# DCDC_stepup.net
KiCad netlist of a schematic drawn in Altium Designer
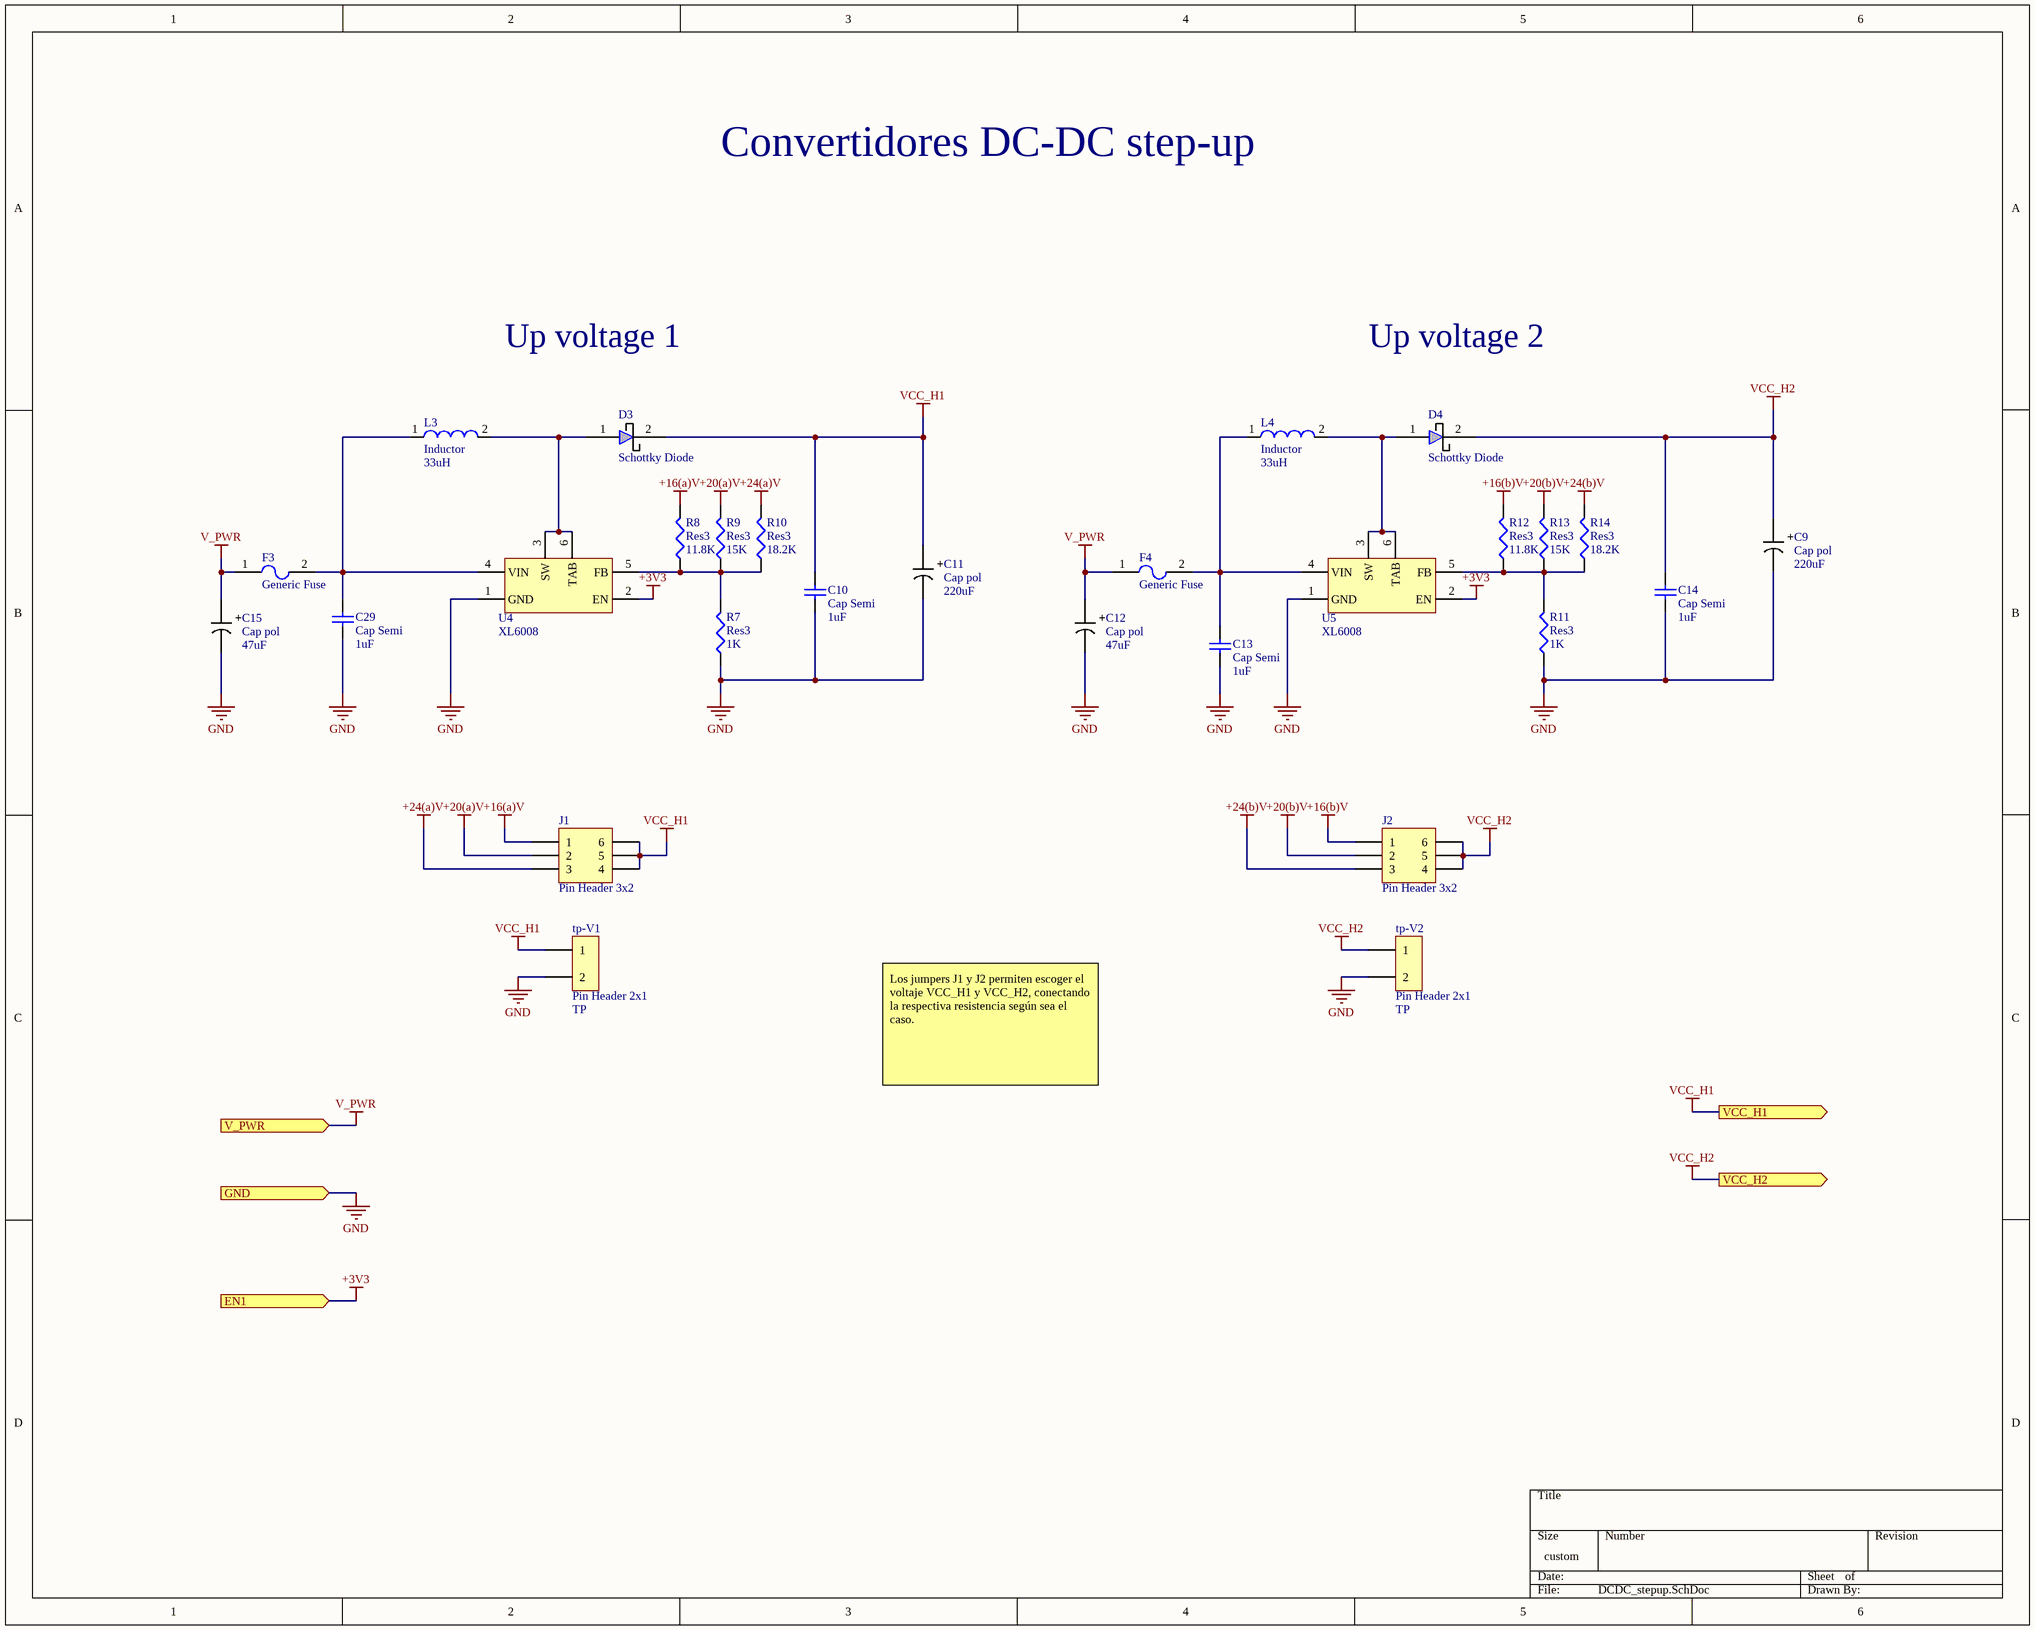
[diagram p0: DCDC_stepup.SchDoc]

(export (version "E")
  (design (tool "Eeschema 10.0.6"))
  (components
    (comp (ref "C9")
      (value "Cap pol")
      (footprint "CAP_SMD_Electrolytic_10x10")
      (description "Electrolytic Aluminium Capacitor")
      (fields
        (field (name "MANUFACTURER") "Lelon")
        (field (name "MANUFACTURER PART NUMBER") "VE-221M1HTR-1010")
        (field (name "ALTIUM_VALUE") "220uF")
      )
      (libsource (lib "IoWLabs") (part "Cap pol"))
    )
    (comp (ref "C10")
      (value "Cap Semi")
      (footprint "1608[0603]")
      (description "Capacitor (Semiconductor SIM Model)")
      (fields
        (field (name "ALTIUM_VALUE") "1uF")
        (field (name "MANUFACTURER") "Samsung Electro-Mechanics")
        (field (name "MANUFACTURER PART NUMBER") "CL10A105KB8NNNC")
        (field (name "PUBLISHER") "Altium Limited")
      )
      (libsource (lib "Miscellaneous Devices") (part "Cap Semi"))
    )
    (comp (ref "C11")
      (value "Cap pol")
      (footprint "CAP_SMD_Electrolytic_10x10")
      (description "Electrolytic Aluminium Capacitor")
      (fields
        (field (name "MANUFACTURER") "Lelon")
        (field (name "MANUFACTURER PART NUMBER") "VE-221M1HTR-1010")
        (field (name "ALTIUM_VALUE") "220uF")
      )
      (libsource (lib "IoWLabs") (part "Cap pol"))
    )
    (comp (ref "C12")
      (value "Cap pol")
      (footprint "CAP_SMD_Electrolytic_10x10")
      (description "Electrolytic Aluminium Capacitor")
      (fields
        (field (name "MANUFACTURER") "Lelon")
        (field (name "MANUFACTURER PART NUMBER") "VEJ470M1HTR-1010")
        (field (name "ALTIUM_VALUE") "47uF")
      )
      (libsource (lib "IoWLabs") (part "Cap pol"))
    )
    (comp (ref "C13")
      (value "Cap Semi")
      (footprint "1608[0603]")
      (description "Capacitor (Semiconductor SIM Model)")
      (fields
        (field (name "ALTIUM_VALUE") "1uF")
        (field (name "MANUFACTURER") "Samsung Electro-Mechanics")
        (field (name "MANUFACTURER PART NUMBER") "CL10A105KB8NNNC")
        (field (name "PUBLISHER") "Altium Limited")
      )
      (libsource (lib "Miscellaneous Devices") (part "Cap Semi"))
    )
    (comp (ref "C14")
      (value "Cap Semi")
      (footprint "1608[0603]")
      (description "Capacitor (Semiconductor SIM Model)")
      (fields
        (field (name "ALTIUM_VALUE") "1uF")
        (field (name "MANUFACTURER") "Samsung Electro-Mechanics")
        (field (name "MANUFACTURER PART NUMBER") "CL10A105KB8NNNC")
        (field (name "PUBLISHER") "Altium Limited")
      )
      (libsource (lib "Miscellaneous Devices") (part "Cap Semi"))
    )
    (comp (ref "C15")
      (value "Cap pol")
      (footprint "CAP_SMD_Electrolytic_10x10")
      (description "Electrolytic Aluminium Capacitor")
      (fields
        (field (name "MANUFACTURER") "Lelon")
        (field (name "MANUFACTURER PART NUMBER") "VEJ470M1HTR-1010")
        (field (name "ALTIUM_VALUE") "47uF")
      )
      (libsource (lib "IoWLabs") (part "Cap pol"))
    )
    (comp (ref "C29")
      (value "Cap Semi")
      (footprint "1608[0603]")
      (description "Capacitor (Semiconductor SIM Model)")
      (fields
        (field (name "ALTIUM_VALUE") "1uF")
        (field (name "MANUFACTURER") "Samsung Electro-Mechanics")
        (field (name "MANUFACTURER PART NUMBER") "CL10A105KB8NNNC")
        (field (name "PUBLISHER") "Altium Limited")
      )
      (libsource (lib "Miscellaneous Devices") (part "Cap Semi"))
    )
    (comp (ref "D3")
      (value "Schottky Diode")
      (footprint "SMB_L4.6-W3.6-LS5.3-RD")
      (description "Schottky Diodes")
      (fields
        (field (name "MANUFACTURER") "MCC(Micro Commercial Components)")
        (field (name "MANUFACTURER PART NUMBER") "SK32B-LTP")
      )
      (libsource (lib "IoWLabs") (part "Schottky Diode"))
    )
    (comp (ref "D4")
      (value "Schottky Diode")
      (footprint "SMB_L4.6-W3.6-LS5.3-RD")
      (description "Schottky Diodes")
      (fields
        (field (name "MANUFACTURER") "MCC(Micro Commercial Components)")
        (field (name "MANUFACTURER PART NUMBER") "SK32B-LTP")
      )
      (libsource (lib "IoWLabs") (part "Schottky Diode"))
    )
    (comp (ref "F3")
      (value "Generic Fuse")
      (footprint "F1206")
      (description "SMD Fuse")
      (fields (field (name "MANUFACTURER") "AEM") (field (name "MANUFACTURER PART NUMBER") "F1206VH4500TM"))
      (libsource (lib "IoWLabs") (part "FUSE"))
    )
    (comp (ref "F4")
      (value "Generic Fuse")
      (footprint "F1206")
      (description "SMD Fuse")
      (fields (field (name "MANUFACTURER") "AEM") (field (name "MANUFACTURER PART NUMBER") "F1206VH4500TM"))
      (libsource (lib "IoWLabs") (part "FUSE"))
    )
    (comp (ref "J1")
      (value "Pin Header 3x2")
      (footprint "HDR-TH_6P-P2.54-V-R2-C3-S2.54_A2541WV-2X3P")
      (description "Pin Header 6pos, 2 row, 2.54 pitch")
      (fields
        (field (name "MANUFACTURER") "CJT(Changjiang Connectors)")
        (field (name "MANUFACTURER PART NUMBER") "A2541WV-2x3P")
      )
      (libsource (lib "IoWLabsConnectors") (part "Header - 3x2c"))
    )
    (comp (ref "J2")
      (value "Pin Header 3x2")
      (footprint "HDR-TH_6P-P2.54-V-R2-C3-S2.54_A2541WV-2X3P")
      (description "Pin Header 6pos, 2 row, 2.54 pitch")
      (fields
        (field (name "MANUFACTURER") "CJT(Changjiang Connectors)")
        (field (name "MANUFACTURER PART NUMBER") "A2541WV-2x3P")
      )
      (libsource (lib "IoWLabsConnectors") (part "Header - 3x2c"))
    )
    (comp (ref "L3")
      (value "Inductor")
      (footprint "IND-SMD_L12.3-W12.3")
      (description "Inductor SMD")
      (fields
        (field (name "MANUFACTURER") "SXN(Shun Xiang Nuo Elec)")
        (field (name "MANUFACTURER PART NUMBER") "SMDRI127-330MT")
        (field (name "ALTIUM_VALUE") "33uH")
      )
      (libsource (lib "IoWLabs") (part "Inductor"))
    )
    (comp (ref "L4")
      (value "Inductor")
      (footprint "IND-SMD_L12.3-W12.3")
      (description "Inductor SMD")
      (fields
        (field (name "MANUFACTURER") "SXN(Shun Xiang Nuo Elec)")
        (field (name "MANUFACTURER PART NUMBER") "SMDRI127-330MT")
        (field (name "ALTIUM_VALUE") "33uH")
      )
      (libsource (lib "IoWLabs") (part "Inductor"))
    )
    (comp (ref "R7")
      (value "Res3")
      (footprint "J1-0603")
      (description "Resistor")
      (fields
        (field (name "ALTIUM_VALUE") "1K")
        (field (name "MANUFACTURER") "KAMAYA")
        (field (name "MANUFACTURER PART NUMBER") "RMC16K102FTP")
        (field (name "PUBLISHER") "Altium Limited")
      )
      (libsource (lib "Miscellaneous Devices") (part "Res3"))
    )
    (comp (ref "R8")
      (value "Res3")
      (footprint "J1-0603")
      (description "Resistor")
      (fields
        (field (name "ALTIUM_VALUE") "11.8K")
        (field (name "MANUFACTURER PART NUMBER") "AC0603FR-0711K8L")
        (field (name "MANUFACTURER") "YAGEO")
        (field (name "PUBLISHER") "Altium Limited")
      )
      (libsource (lib "Miscellaneous Devices") (part "Res3"))
    )
    (comp (ref "R9")
      (value "Res3")
      (footprint "J1-0603")
      (description "Resistor")
      (fields
        (field (name "ALTIUM_VALUE") "15K")
        (field (name "MANUFACTURER") "YAGEO")
        (field (name "MANUFACTURER PART NUMBER") "RC0603FR-0715KL")
        (field (name "PUBLISHER") "Altium Limited")
      )
      (libsource (lib "Miscellaneous Devices") (part "Res3"))
    )
    (comp (ref "R10")
      (value "Res3")
      (footprint "J1-0603")
      (description "Resistor")
      (fields
        (field (name "ALTIUM_VALUE") "18.2K")
        (field (name "MANUFACTURER") "RALEC")
        (field (name "MANUFACTURER PART NUMBER") "RTT031822FTP")
        (field (name "PUBLISHER") "Altium Limited")
      )
      (libsource (lib "Miscellaneous Devices") (part "Res3"))
    )
    (comp (ref "R11")
      (value "Res3")
      (footprint "J1-0603")
      (description "Resistor")
      (fields
        (field (name "ALTIUM_VALUE") "1K")
        (field (name "MANUFACTURER") "KAMAYA")
        (field (name "MANUFACTURER PART NUMBER") "RMC16K102FTP")
        (field (name "PUBLISHER") "Altium Limited")
      )
      (libsource (lib "Miscellaneous Devices") (part "Res3"))
    )
    (comp (ref "R12")
      (value "Res3")
      (footprint "J1-0603")
      (description "Resistor")
      (fields
        (field (name "ALTIUM_VALUE") "11.8K")
        (field (name "MANUFACTURER PART NUMBER") "AC0603FR-0711K8L")
        (field (name "MANUFACTURER") "YAGEO")
        (field (name "PUBLISHER") "Altium Limited")
      )
      (libsource (lib "Miscellaneous Devices") (part "Res3"))
    )
    (comp (ref "R13")
      (value "Res3")
      (footprint "J1-0603")
      (description "Resistor")
      (fields
        (field (name "ALTIUM_VALUE") "15K")
        (field (name "MANUFACTURER") "YAGEO")
        (field (name "MANUFACTURER PART NUMBER") "RC0603FR-0715KL")
        (field (name "PUBLISHER") "Altium Limited")
      )
      (libsource (lib "Miscellaneous Devices") (part "Res3"))
    )
    (comp (ref "R14")
      (value "Res3")
      (footprint "J1-0603")
      (description "Resistor")
      (fields
        (field (name "ALTIUM_VALUE") "18.2K")
        (field (name "MANUFACTURER") "RALEC")
        (field (name "MANUFACTURER PART NUMBER") "RTT031822FTP")
        (field (name "PUBLISHER") "Altium Limited")
      )
      (libsource (lib "Miscellaneous Devices") (part "Res3"))
    )
    (comp (ref "tp-V1")
      (value "Pin Header 2x1")
      (footprint "HDR-TH_P2.54-H-M_A2541WV-2P")
      (description "Pin Header 2pos, 1 row, 2.54 pitch")
      (fields
        (field (name "MANUFACTURER") "CJT(Changjiang Connectors)")
        (field (name "MANUFACTURER PART NUMBER") "A2541WV-2P")
      )
      (libsource (lib "IoWLabsConnectors") (part "Header - 2x1c"))
    )
    (comp (ref "tp-V2")
      (value "Pin Header 2x1")
      (footprint "HDR-TH_P2.54-H-M_A2541WV-2P")
      (description "Pin Header 2pos, 1 row, 2.54 pitch")
      (fields
        (field (name "MANUFACTURER") "CJT(Changjiang Connectors)")
        (field (name "MANUFACTURER PART NUMBER") "A2541WV-2P")
      )
      (libsource (lib "IoWLabsConnectors") (part "Header - 2x1c"))
    )
    (comp (ref "U4")
      (value "XL6008")
      (footprint "TO-252-5")
      (description "DC-DC Converters Step-Up, Step-Up/Step-Down Adjustable 1 3.6V 32V 3A TO-252-5 RoHS")
      (fields (field (name "MANUFACTURER") "XLSEMI") (field (name "MANUFACTURER PART NUMBER") "XL6008E1"))
      (libsource (lib "IoWLabs") (part "XL6008"))
    )
    (comp (ref "U5")
      (value "XL6008")
      (footprint "TO-252-5")
      (description "DC-DC Converters Step-Up, Step-Up/Step-Down Adjustable 1 3.6V 32V 3A TO-252-5 RoHS")
      (fields (field (name "MANUFACTURER") "XLSEMI") (field (name "MANUFACTURER PART NUMBER") "XL6008E1"))
      (libsource (lib "IoWLabs") (part "XL6008"))
    )
  )
  (nets
    (net (code "1") (name "+3V3") (class "Default")
      (node (ref "U4") (pin "2") (pinfunction "EN_2") (pintype "passive"))
      (node (ref "U5") (pin "2") (pinfunction "EN_2") (pintype "passive"))
    )
    (net (code "2") (name "+16(a)V") (class "Default")
      (node (ref "J1") (pin "1") (pinfunction "1_1") (pintype "passive"))
      (node (ref "R8") (pin "2") (pinfunction "2_2") (pintype "passive"))
    )
    (net (code "3") (name "+16(b)V") (class "Default")
      (node (ref "J2") (pin "1") (pinfunction "1_1") (pintype "passive"))
      (node (ref "R12") (pin "2") (pinfunction "2_2") (pintype "passive"))
    )
    (net (code "4") (name "+20(a)V") (class "Default")
      (node (ref "J1") (pin "2") (pinfunction "2_2") (pintype "passive"))
      (node (ref "R9") (pin "2") (pinfunction "2_2") (pintype "passive"))
    )
    (net (code "5") (name "+20(b)V") (class "Default")
      (node (ref "J2") (pin "2") (pinfunction "2_2") (pintype "passive"))
      (node (ref "R13") (pin "2") (pinfunction "2_2") (pintype "passive"))
    )
    (net (code "6") (name "+24(a)V") (class "Default")
      (node (ref "J1") (pin "3") (pinfunction "3_3") (pintype "passive"))
      (node (ref "R10") (pin "2") (pinfunction "2_2") (pintype "passive"))
    )
    (net (code "7") (name "+24(b)V") (class "Default")
      (node (ref "J2") (pin "3") (pinfunction "3_3") (pintype "passive"))
      (node (ref "R14") (pin "2") (pinfunction "2_2") (pintype "passive"))
    )
    (net (code "8") (name "GND") (class "Default")
      (node (ref "C10") (pin "1") (pinfunction "1_1") (pintype "passive"))
      (node (ref "C11") (pin "1") (pinfunction "1_1") (pintype "passive"))
      (node (ref "C12") (pin "1") (pinfunction "1_1") (pintype "passive"))
      (node (ref "C13") (pin "1") (pinfunction "1_1") (pintype "passive"))
      (node (ref "C14") (pin "1") (pinfunction "1_1") (pintype "passive"))
      (node (ref "C15") (pin "1") (pinfunction "1_1") (pintype "passive"))
      (node (ref "C29") (pin "1") (pinfunction "1_1") (pintype "passive"))
      (node (ref "C9") (pin "1") (pinfunction "1_1") (pintype "passive"))
      (node (ref "R11") (pin "1") (pinfunction "1_1") (pintype "passive"))
      (node (ref "R7") (pin "1") (pinfunction "1_1") (pintype "passive"))
      (node (ref "U4") (pin "1") (pinfunction "GND_1") (pintype "passive"))
      (node (ref "U5") (pin "1") (pinfunction "GND_1") (pintype "passive"))
      (node (ref "tp-V1") (pin "2") (pinfunction "2_2") (pintype "passive"))
      (node (ref "tp-V2") (pin "2") (pinfunction "2_2") (pintype "passive"))
    )
    (net (code "9") (name "Net-(D3-+)") (class "Default")
      (node (ref "D3") (pin "1") (pinfunction "+_1") (pintype "passive"))
      (node (ref "L3") (pin "2") (pinfunction "2_2") (pintype "passive"))
      (node (ref "U4") (pin "3") (pinfunction "SW_3") (pintype "passive"))
      (node (ref "U4") (pin "6") (pinfunction "TAB_6") (pintype "passive"))
    )
    (net (code "10") (name "Net-(D4-+)") (class "Default")
      (node (ref "D4") (pin "1") (pinfunction "+_1") (pintype "passive"))
      (node (ref "L4") (pin "2") (pinfunction "2_2") (pintype "passive"))
      (node (ref "U5") (pin "3") (pinfunction "SW_3") (pintype "passive"))
      (node (ref "U5") (pin "6") (pinfunction "TAB_6") (pintype "passive"))
    )
    (net (code "11") (name "Net-(U4-FB)") (class "Default")
      (node (ref "R10") (pin "1") (pinfunction "1_1") (pintype "passive"))
      (node (ref "R7") (pin "2") (pinfunction "2_2") (pintype "passive"))
      (node (ref "R8") (pin "1") (pinfunction "1_1") (pintype "passive"))
      (node (ref "R9") (pin "1") (pinfunction "1_1") (pintype "passive"))
      (node (ref "U4") (pin "5") (pinfunction "FB_5") (pintype "passive"))
    )
    (net (code "12") (name "Net-(U4-VIN)") (class "Default")
      (node (ref "C29") (pin "2") (pinfunction "2_2") (pintype "passive"))
      (node (ref "F3") (pin "2") (pinfunction "2_2") (pintype "passive"))
      (node (ref "L3") (pin "1") (pinfunction "1_1") (pintype "passive"))
      (node (ref "U4") (pin "4") (pinfunction "VIN_4") (pintype "passive"))
    )
    (net (code "13") (name "Net-(U5-FB)") (class "Default")
      (node (ref "R11") (pin "2") (pinfunction "2_2") (pintype "passive"))
      (node (ref "R12") (pin "1") (pinfunction "1_1") (pintype "passive"))
      (node (ref "R13") (pin "1") (pinfunction "1_1") (pintype "passive"))
      (node (ref "R14") (pin "1") (pinfunction "1_1") (pintype "passive"))
      (node (ref "U5") (pin "5") (pinfunction "FB_5") (pintype "passive"))
    )
    (net (code "14") (name "Net-(U5-VIN)") (class "Default")
      (node (ref "C13") (pin "2") (pinfunction "2_2") (pintype "passive"))
      (node (ref "F4") (pin "2") (pinfunction "2_2") (pintype "passive"))
      (node (ref "L4") (pin "1") (pinfunction "1_1") (pintype "passive"))
      (node (ref "U5") (pin "4") (pinfunction "VIN_4") (pintype "passive"))
    )
    (net (code "15") (name "VCC_H1") (class "Default")
      (node (ref "C10") (pin "2") (pinfunction "2_2") (pintype "passive"))
      (node (ref "C11") (pin "2") (pinfunction "2_2") (pintype "passive"))
      (node (ref "D3") (pin "2") (pinfunction "-_2") (pintype "passive"))
      (node (ref "J1") (pin "4") (pinfunction "4_4") (pintype "passive"))
      (node (ref "J1") (pin "5") (pinfunction "5_5") (pintype "passive"))
      (node (ref "J1") (pin "6") (pinfunction "6_6") (pintype "passive"))
      (node (ref "tp-V1") (pin "1") (pinfunction "1_1") (pintype "passive"))
    )
    (net (code "16") (name "VCC_H2") (class "Default")
      (node (ref "C14") (pin "2") (pinfunction "2_2") (pintype "passive"))
      (node (ref "C9") (pin "2") (pinfunction "2_2") (pintype "passive"))
      (node (ref "D4") (pin "2") (pinfunction "-_2") (pintype "passive"))
      (node (ref "J2") (pin "4") (pinfunction "4_4") (pintype "passive"))
      (node (ref "J2") (pin "5") (pinfunction "5_5") (pintype "passive"))
      (node (ref "J2") (pin "6") (pinfunction "6_6") (pintype "passive"))
      (node (ref "tp-V2") (pin "1") (pinfunction "1_1") (pintype "passive"))
    )
    (net (code "17") (name "V_PWR") (class "Default")
      (node (ref "C12") (pin "2") (pinfunction "2_2") (pintype "passive"))
      (node (ref "C15") (pin "2") (pinfunction "2_2") (pintype "passive"))
      (node (ref "F3") (pin "1") (pinfunction "1_1") (pintype "passive"))
      (node (ref "F4") (pin "1") (pinfunction "1_1") (pintype "passive"))
    )
  )
)
